# ARE_adaptadora_Propeller_40pin.net
KiCad netlist of a schematic drawn in EAGLE
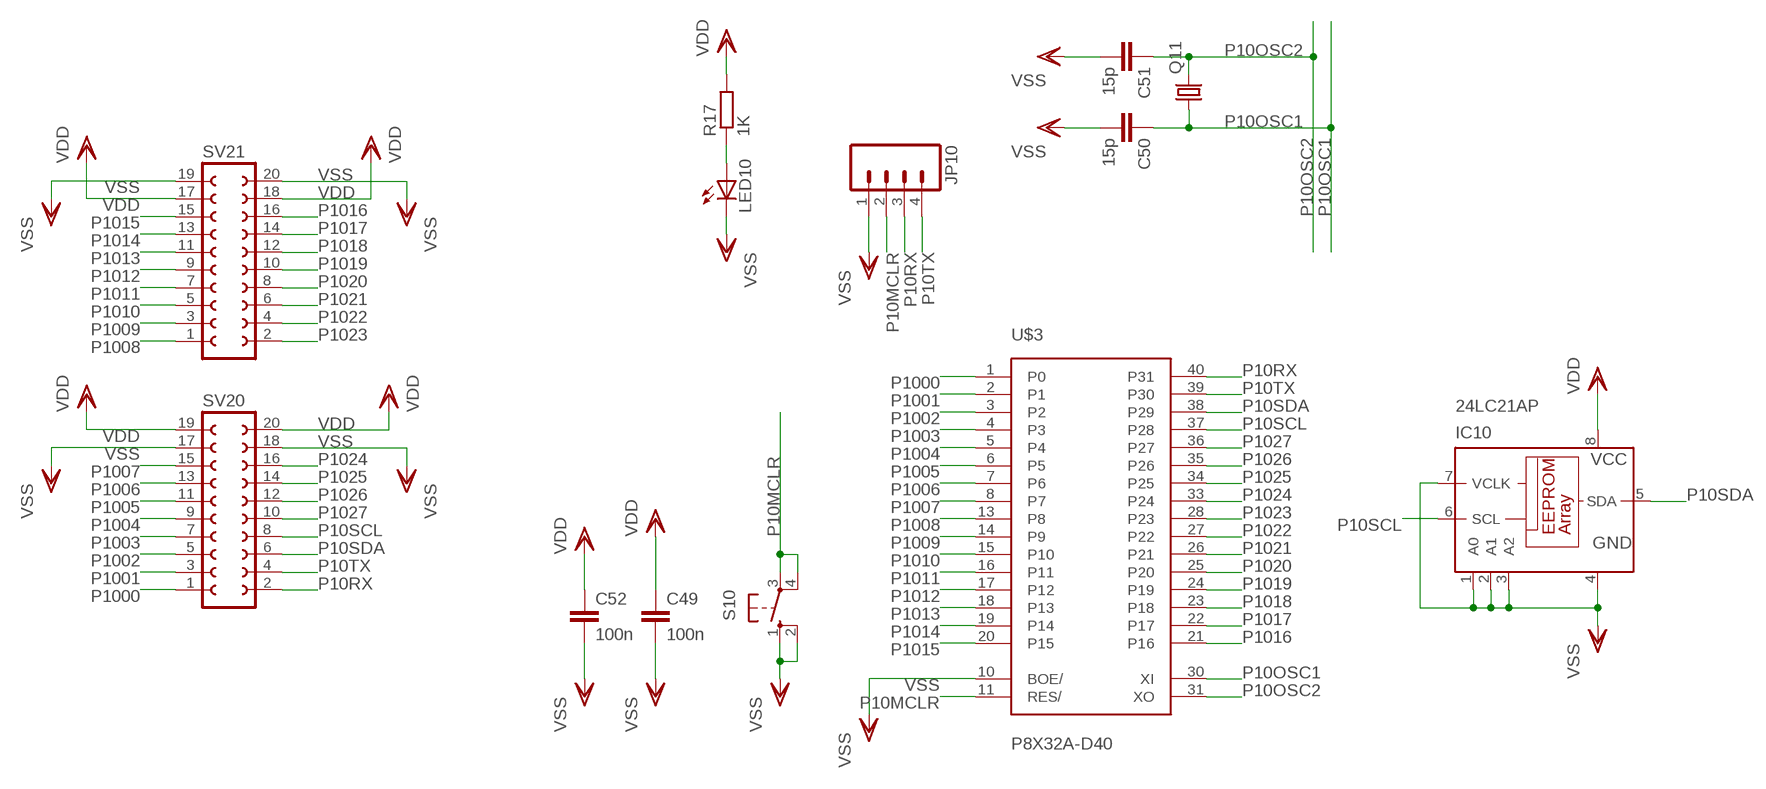
[diagram p0: schematic, sheet 1]

(export (version "E")
  (design (tool "Eeschema 10.0.6"))
  (components
    (comp (ref "C49")
      (value "100n")
      (footprint "eagle-import:C0805")
      (libsource (lib "eagle-import") (part "C-EUC0805"))
    )
    (comp (ref "C50")
      (value "15p")
      (footprint "eagle-import:C0805")
      (libsource (lib "eagle-import") (part "C-EUC0805"))
    )
    (comp (ref "C51")
      (value "15p")
      (footprint "eagle-import:C0805")
      (libsource (lib "eagle-import") (part "C-EUC0805"))
    )
    (comp (ref "C52")
      (value "100n")
      (footprint "eagle-import:C0805")
      (libsource (lib "eagle-import") (part "C-EUC0805"))
    )
    (comp (ref "IC10")
      (value "24LC21AP")
      (footprint "eagle-import:DIL8")
      (libsource (lib "eagle-import") (part "24LPC21A"))
    )
    (comp (ref "JP10")
      (value "M04PTH")
      (footprint "eagle-import:1X04")
      (libsource (lib "eagle-import") (part "M04PTH"))
    )
    (comp (ref "LED10")
      (value "LED3MM")
      (footprint "eagle-import:LED3MM")
      (libsource (lib "eagle-import") (part "LED3MM"))
    )
    (comp (ref "Q11")
      (value "CRYSTALHC18U-V")
      (footprint "eagle-import:HC18U-V")
      (libsource (lib "eagle-import") (part "CRYSTALHC18U-V"))
    )
    (comp (ref "R17")
      (value "1K")
      (footprint "eagle-import:R0805")
      (libsource (lib "eagle-import") (part "R-EU_R0805"))
    )
    (comp (ref "S10")
      (value "10-XX")
      (footprint "eagle-import:B3F-10XX")
      (fields
        (field (name "MPN") "B3F-1000")
        (field (name "MPN_1") "B3F-1000")
        (field (name "OC_FARNELL") "176432")
        (field (name "OC_NEWARK") "36M3542")
      )
      (libsource (lib "eagle-import") (part "10-XX"))
    )
    (comp (ref "SV20")
      (value "FE10-2W")
      (footprint "eagle-import:FE10-2W")
      (libsource (lib "eagle-import") (part "FE10-2W"))
    )
    (comp (ref "SV21")
      (value "FE10-2W")
      (footprint "eagle-import:FE10-2W")
      (fields (field (name "OC_FARNELL") "unknown") (field (name "OC_NEWARK") "unknown"))
      (libsource (lib "eagle-import") (part "FE10-2W"))
    )
    (comp (ref "U$3")
      (value "P8X32A-D40")
      (footprint "eagle-import:P8X32A-D40")
      (libsource (lib "eagle-import") (part "P8X32A-D40"))
    )
  )
  (nets
    (net (code "1") (name "/P10MCLR") (class "Default")
      (node (ref "JP10") (pin "2") (pinfunction "2_2") (pintype "passive"))
      (node (ref "S10") (pin "3") (pinfunction "P_3") (pintype "passive"))
      (node (ref "S10") (pin "4") (pinfunction "P1_4") (pintype "passive"))
      (node (ref "U$3") (pin "11") (pinfunction "RES/_11") (pintype "bidirectional"))
    )
    (net (code "2") (name "/P10OSC1") (class "Default")
      (node (ref "C50") (pin "1") (pinfunction "1_1") (pintype "passive"))
      (node (ref "Q11") (pin "1") (pinfunction "1_1") (pintype "passive"))
      (node (ref "U$3") (pin "30") (pinfunction "XI_30") (pintype "input"))
    )
    (net (code "3") (name "/P10OSC2") (class "Default")
      (node (ref "C51") (pin "1") (pinfunction "1_1") (pintype "passive"))
      (node (ref "Q11") (pin "2") (pinfunction "2_2") (pintype "passive"))
      (node (ref "U$3") (pin "31") (pinfunction "XO_31") (pintype "output"))
    )
    (net (code "4") (name "/P10RX") (class "Default")
      (node (ref "JP10") (pin "3") (pinfunction "3_3") (pintype "passive"))
      (node (ref "SV20") (pin "2") (pinfunction "2_2") (pintype "passive"))
      (node (ref "U$3") (pin "40") (pinfunction "P31_40") (pintype "bidirectional"))
    )
    (net (code "5") (name "/P10SCL") (class "Default")
      (node (ref "IC10") (pin "6") (pinfunction "SCL_6") (pintype "input"))
      (node (ref "SV20") (pin "8") (pinfunction "8_8") (pintype "passive"))
      (node (ref "U$3") (pin "37") (pinfunction "P28_37") (pintype "bidirectional"))
    )
    (net (code "6") (name "/P10SDA") (class "Default")
      (node (ref "IC10") (pin "5") (pinfunction "SDA_5") (pintype "bidirectional"))
      (node (ref "SV20") (pin "6") (pinfunction "6_6") (pintype "passive"))
      (node (ref "U$3") (pin "38") (pinfunction "P29_38") (pintype "bidirectional"))
    )
    (net (code "7") (name "/P10TX") (class "Default")
      (node (ref "JP10") (pin "4") (pinfunction "4_4") (pintype "passive"))
      (node (ref "SV20") (pin "4") (pinfunction "4_4") (pintype "passive"))
      (node (ref "U$3") (pin "39") (pinfunction "P30_39") (pintype "bidirectional"))
    )
    (net (code "8") (name "/P1000") (class "Default")
      (node (ref "SV20") (pin "1") (pinfunction "1_1") (pintype "passive"))
      (node (ref "U$3") (pin "1") (pinfunction "P0_1") (pintype "bidirectional"))
    )
    (net (code "9") (name "/P1001") (class "Default")
      (node (ref "SV20") (pin "3") (pinfunction "3_3") (pintype "passive"))
      (node (ref "U$3") (pin "2") (pinfunction "P1_2") (pintype "bidirectional"))
    )
    (net (code "10") (name "/P1002") (class "Default")
      (node (ref "SV20") (pin "5") (pinfunction "5_5") (pintype "passive"))
      (node (ref "U$3") (pin "3") (pinfunction "P2_3") (pintype "bidirectional"))
    )
    (net (code "11") (name "/P1003") (class "Default")
      (node (ref "SV20") (pin "7") (pinfunction "7_7") (pintype "passive"))
      (node (ref "U$3") (pin "4") (pinfunction "P3_4") (pintype "bidirectional"))
    )
    (net (code "12") (name "/P1004") (class "Default")
      (node (ref "SV20") (pin "9") (pinfunction "9_9") (pintype "passive"))
      (node (ref "U$3") (pin "5") (pinfunction "P4_5") (pintype "bidirectional"))
    )
    (net (code "13") (name "/P1005") (class "Default")
      (node (ref "SV20") (pin "11") (pinfunction "11_11") (pintype "passive"))
      (node (ref "U$3") (pin "6") (pinfunction "P5_6") (pintype "bidirectional"))
    )
    (net (code "14") (name "/P1006") (class "Default")
      (node (ref "SV20") (pin "13") (pinfunction "13_13") (pintype "passive"))
      (node (ref "U$3") (pin "7") (pinfunction "P6_7") (pintype "bidirectional"))
    )
    (net (code "15") (name "/P1007") (class "Default")
      (node (ref "SV20") (pin "15") (pinfunction "15_15") (pintype "passive"))
      (node (ref "U$3") (pin "8") (pinfunction "P7_8") (pintype "bidirectional"))
    )
    (net (code "16") (name "/P1008") (class "Default")
      (node (ref "SV21") (pin "1") (pinfunction "1_1") (pintype "passive"))
      (node (ref "U$3") (pin "13") (pinfunction "P8_13") (pintype "bidirectional"))
    )
    (net (code "17") (name "/P1009") (class "Default")
      (node (ref "SV21") (pin "3") (pinfunction "3_3") (pintype "passive"))
      (node (ref "U$3") (pin "14") (pinfunction "P9_14") (pintype "bidirectional"))
    )
    (net (code "18") (name "/P1010") (class "Default")
      (node (ref "SV21") (pin "5") (pinfunction "5_5") (pintype "passive"))
      (node (ref "U$3") (pin "15") (pinfunction "P10_15") (pintype "bidirectional"))
    )
    (net (code "19") (name "/P1011") (class "Default")
      (node (ref "SV21") (pin "7") (pinfunction "7_7") (pintype "passive"))
      (node (ref "U$3") (pin "16") (pinfunction "P11_16") (pintype "bidirectional"))
    )
    (net (code "20") (name "/P1012") (class "Default")
      (node (ref "SV21") (pin "9") (pinfunction "9_9") (pintype "passive"))
      (node (ref "U$3") (pin "17") (pinfunction "P12_17") (pintype "bidirectional"))
    )
    (net (code "21") (name "/P1013") (class "Default")
      (node (ref "SV21") (pin "11") (pinfunction "11_11") (pintype "passive"))
      (node (ref "U$3") (pin "18") (pinfunction "P13_18") (pintype "bidirectional"))
    )
    (net (code "22") (name "/P1014") (class "Default")
      (node (ref "SV21") (pin "13") (pinfunction "13_13") (pintype "passive"))
      (node (ref "U$3") (pin "19") (pinfunction "P14_19") (pintype "bidirectional"))
    )
    (net (code "23") (name "/P1015") (class "Default")
      (node (ref "SV21") (pin "15") (pinfunction "15_15") (pintype "passive"))
      (node (ref "U$3") (pin "20") (pinfunction "P15_20") (pintype "bidirectional"))
    )
    (net (code "24") (name "/P1016") (class "Default")
      (node (ref "SV21") (pin "16") (pinfunction "16_16") (pintype "passive"))
      (node (ref "U$3") (pin "21") (pinfunction "P16_21") (pintype "bidirectional"))
    )
    (net (code "25") (name "/P1017") (class "Default")
      (node (ref "SV21") (pin "14") (pinfunction "14_14") (pintype "passive"))
      (node (ref "U$3") (pin "22") (pinfunction "P17_22") (pintype "bidirectional"))
    )
    (net (code "26") (name "/P1018") (class "Default")
      (node (ref "SV21") (pin "12") (pinfunction "12_12") (pintype "passive"))
      (node (ref "U$3") (pin "23") (pinfunction "P18_23") (pintype "bidirectional"))
    )
    (net (code "27") (name "/P1019") (class "Default")
      (node (ref "SV21") (pin "10") (pinfunction "10_10") (pintype "passive"))
      (node (ref "U$3") (pin "24") (pinfunction "P19_24") (pintype "bidirectional"))
    )
    (net (code "28") (name "/P1020") (class "Default")
      (node (ref "SV21") (pin "8") (pinfunction "8_8") (pintype "passive"))
      (node (ref "U$3") (pin "25") (pinfunction "P20_25") (pintype "bidirectional"))
    )
    (net (code "29") (name "/P1021") (class "Default")
      (node (ref "SV21") (pin "6") (pinfunction "6_6") (pintype "passive"))
      (node (ref "U$3") (pin "26") (pinfunction "P21_26") (pintype "bidirectional"))
    )
    (net (code "30") (name "/P1022") (class "Default")
      (node (ref "SV21") (pin "4") (pinfunction "4_4") (pintype "passive"))
      (node (ref "U$3") (pin "27") (pinfunction "P22_27") (pintype "bidirectional"))
    )
    (net (code "31") (name "/P1023") (class "Default")
      (node (ref "SV21") (pin "2") (pinfunction "2_2") (pintype "passive"))
      (node (ref "U$3") (pin "28") (pinfunction "P23_28") (pintype "bidirectional"))
    )
    (net (code "32") (name "/P1024") (class "Default")
      (node (ref "SV20") (pin "16") (pinfunction "16_16") (pintype "passive"))
      (node (ref "U$3") (pin "33") (pinfunction "P24_33") (pintype "bidirectional"))
    )
    (net (code "33") (name "/P1025") (class "Default")
      (node (ref "SV20") (pin "14") (pinfunction "14_14") (pintype "passive"))
      (node (ref "U$3") (pin "34") (pinfunction "P25_34") (pintype "bidirectional"))
    )
    (net (code "34") (name "/P1026") (class "Default")
      (node (ref "SV20") (pin "12") (pinfunction "12_12") (pintype "passive"))
      (node (ref "U$3") (pin "35") (pinfunction "P26_35") (pintype "bidirectional"))
    )
    (net (code "35") (name "/P1027") (class "Default")
      (node (ref "SV20") (pin "10") (pinfunction "10_10") (pintype "passive"))
      (node (ref "U$3") (pin "36") (pinfunction "P27_36") (pintype "bidirectional"))
    )
    (net (code "36") (name "Net-(LED10-PadA)") (class "Default")
      (node (ref "LED10") (pin "A") (pinfunction "A_A") (pintype "passive"))
      (node (ref "R17") (pin "1") (pinfunction "1_1") (pintype "passive"))
    )
    (net (code "37") (name "VDD") (class "Default")
      (node (ref "C49") (pin "1") (pinfunction "1_1") (pintype "passive"))
      (node (ref "C52") (pin "1") (pinfunction "1_1") (pintype "passive"))
      (node (ref "IC10") (pin "8") (pinfunction "VCC_8") (pintype "power_in"))
      (node (ref "R17") (pin "2") (pinfunction "2_2") (pintype "passive"))
      (node (ref "SV20") (pin "19") (pinfunction "19_19") (pintype "passive"))
      (node (ref "SV20") (pin "20") (pinfunction "20_20") (pintype "passive"))
      (node (ref "SV21") (pin "17") (pinfunction "17_17") (pintype "passive"))
      (node (ref "SV21") (pin "18") (pinfunction "18_18") (pintype "passive"))
    )
    (net (code "38") (name "VSS") (class "Default")
      (node (ref "C49") (pin "2") (pinfunction "2_2") (pintype "passive"))
      (node (ref "C50") (pin "2") (pinfunction "2_2") (pintype "passive"))
      (node (ref "C51") (pin "2") (pinfunction "2_2") (pintype "passive"))
      (node (ref "C52") (pin "2") (pinfunction "2_2") (pintype "passive"))
      (node (ref "IC10") (pin "1") (pinfunction "A0_1") (pintype "bidirectional"))
      (node (ref "IC10") (pin "2") (pinfunction "A1_2") (pintype "bidirectional"))
      (node (ref "IC10") (pin "3") (pinfunction "A2_3") (pintype "bidirectional"))
      (node (ref "IC10") (pin "4") (pinfunction "GND_4") (pintype "power_in"))
      (node (ref "IC10") (pin "7") (pinfunction "VCLK_7") (pintype "input"))
      (node (ref "JP10") (pin "1") (pinfunction "1_1") (pintype "passive"))
      (node (ref "LED10") (pin "K") (pinfunction "C_K") (pintype "passive"))
      (node (ref "S10") (pin "1") (pinfunction "S_1") (pintype "passive"))
      (node (ref "S10") (pin "2") (pinfunction "S1_2") (pintype "passive"))
      (node (ref "SV20") (pin "17") (pinfunction "17_17") (pintype "passive"))
      (node (ref "SV20") (pin "18") (pinfunction "18_18") (pintype "passive"))
      (node (ref "SV21") (pin "19") (pinfunction "19_19") (pintype "passive"))
      (node (ref "SV21") (pin "20") (pinfunction "20_20") (pintype "passive"))
      (node (ref "U$3") (pin "10") (pinfunction "BOE/_10") (pintype "input"))
    )
  )
)
